# doorbellUSB.net
KiCad netlist of a schematic drawn in EAGLE
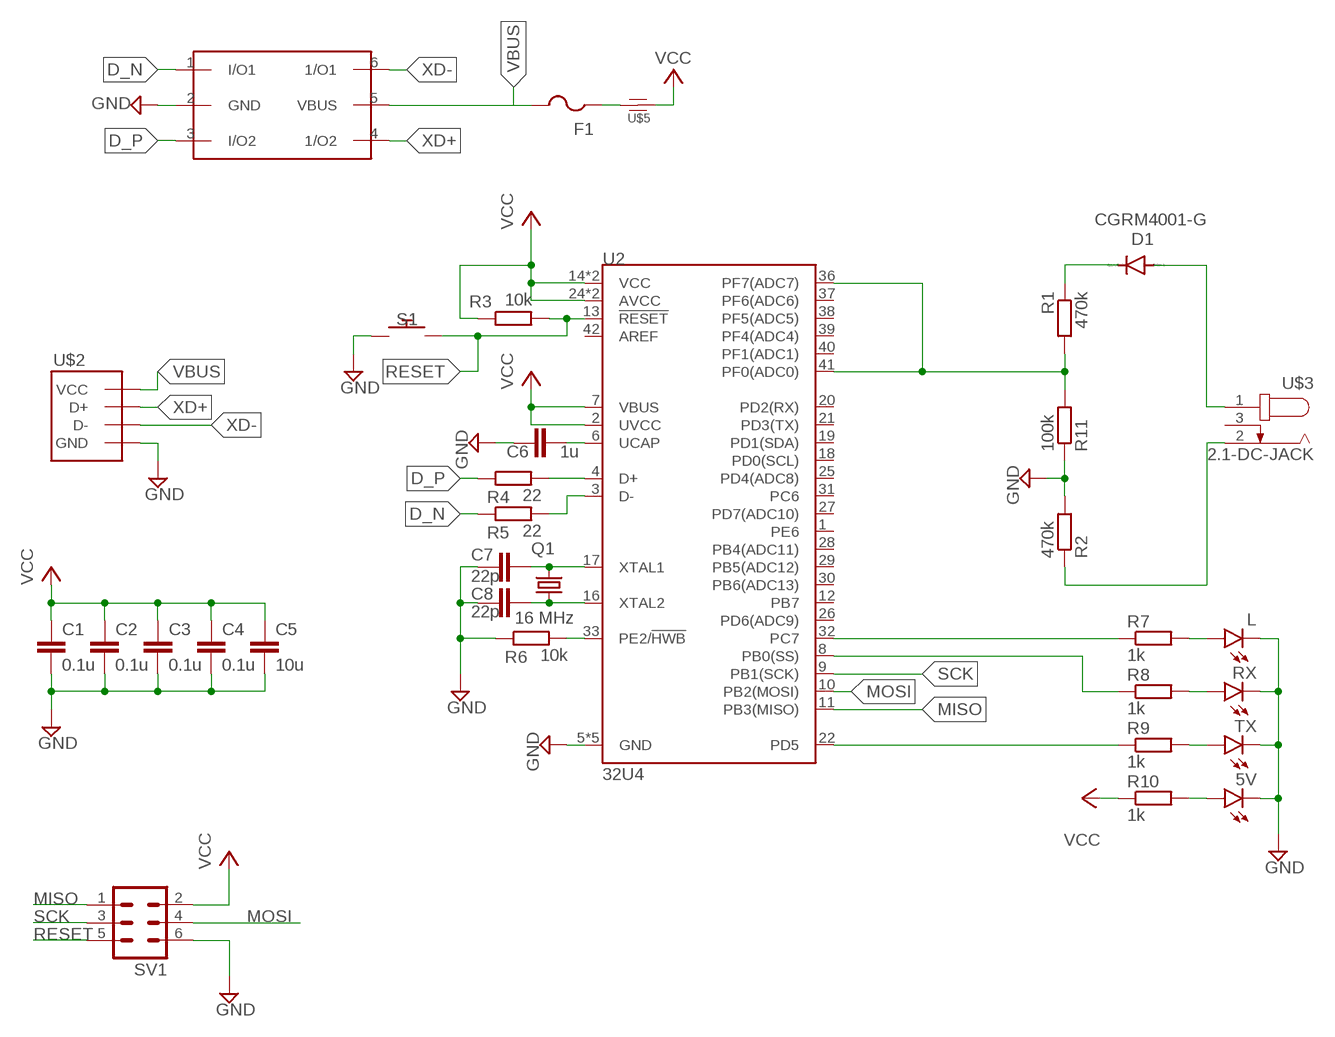
[diagram p0: schematic, sheet 1]

(export (version "E")
  (design (tool "Eeschema 10.0.6"))
  (components
    (comp (ref "5V")
      (value "LEDCHIP-LED0805")
      (footprint "eagle-import:CHIP-LED0805")
      (libsource (lib "eagle-import") (part "LEDCHIP-LED0805"))
    )
    (comp (ref "C1")
      (value "0.1u")
      (footprint "eagle-import:C0805")
      (libsource (lib "eagle-import") (part "C-EUC0805"))
    )
    (comp (ref "C2")
      (value "0.1u")
      (footprint "eagle-import:C0805")
      (libsource (lib "eagle-import") (part "C-EUC0805"))
    )
    (comp (ref "C3")
      (value "0.1u")
      (footprint "eagle-import:C0805")
      (libsource (lib "eagle-import") (part "C-EUC0805"))
    )
    (comp (ref "C4")
      (value "0.1u")
      (footprint "eagle-import:C0805")
      (libsource (lib "eagle-import") (part "C-EUC0805"))
    )
    (comp (ref "C5")
      (value "10u")
      (footprint "eagle-import:C0805")
      (libsource (lib "eagle-import") (part "C-EUC0805"))
    )
    (comp (ref "C6")
      (value "1u")
      (footprint "eagle-import:C0805")
      (libsource (lib "eagle-import") (part "C-EUC0805"))
    )
    (comp (ref "C7")
      (value "22p")
      (footprint "eagle-import:C0805")
      (libsource (lib "eagle-import") (part "C-EUC0805"))
    )
    (comp (ref "C8")
      (value "22p")
      (footprint "eagle-import:C0805")
      (libsource (lib "eagle-import") (part "C-EUC0805"))
    )
    (comp (ref "D1")
      (value "CGRM4001-G")
      (footprint "eagle-import:SOD-123_MINI-SMA")
      (libsource (lib "eagle-import") (part "CGRM400-G1"))
    )
    (comp (ref "F1")
      (value "PTCFUSE-1812")
      (footprint "eagle-import:1812")
      (libsource (lib "eagle-import") (part "PTCFUSE-1812"))
    )
    (comp (ref "L")
      (value "LEDCHIP-LED0805")
      (footprint "eagle-import:CHIP-LED0805")
      (libsource (lib "eagle-import") (part "LEDCHIP-LED0805"))
    )
    (comp (ref "Q1")
      (value "16 MHz")
      (footprint "eagle-import:5.0X3.2_2")
      (libsource (lib "eagle-import") (part "KX-9B"))
    )
    (comp (ref "R1")
      (value "470k")
      (footprint "eagle-import:R0805")
      (libsource (lib "eagle-import") (part "R-EU_R0805"))
    )
    (comp (ref "R2")
      (value "470k")
      (footprint "eagle-import:R0805")
      (libsource (lib "eagle-import") (part "R-EU_R0805"))
    )
    (comp (ref "R3")
      (value "10k")
      (footprint "eagle-import:R0805")
      (libsource (lib "eagle-import") (part "R-EU_R0805"))
    )
    (comp (ref "R4")
      (value "22")
      (footprint "eagle-import:R0805")
      (libsource (lib "eagle-import") (part "R-EU_R0805"))
    )
    (comp (ref "R5")
      (value "22")
      (footprint "eagle-import:R0805")
      (libsource (lib "eagle-import") (part "R-EU_R0805"))
    )
    (comp (ref "R6")
      (value "10k")
      (footprint "eagle-import:R0805")
      (libsource (lib "eagle-import") (part "R-EU_R0805"))
    )
    (comp (ref "R7")
      (value "1k")
      (footprint "eagle-import:R0805")
      (libsource (lib "eagle-import") (part "R-EU_R0805"))
    )
    (comp (ref "R8")
      (value "1k")
      (footprint "eagle-import:R0805")
      (libsource (lib "eagle-import") (part "R-EU_R0805"))
    )
    (comp (ref "R9")
      (value "1k")
      (footprint "eagle-import:R0805")
      (libsource (lib "eagle-import") (part "R-EU_R0805"))
    )
    (comp (ref "R10")
      (value "1k")
      (footprint "eagle-import:R0805")
      (libsource (lib "eagle-import") (part "R-EU_R0805"))
    )
    (comp (ref "R11")
      (value "100k")
      (footprint "eagle-import:R0805")
      (libsource (lib "eagle-import") (part "R-EU_R0805"))
    )
    (comp (ref "RX")
      (value "LEDCHIP-LED0805")
      (footprint "eagle-import:CHIP-LED0805")
      (libsource (lib "eagle-import") (part "LEDCHIP-LED0805"))
    )
    (comp (ref "S1")
      (value "3X4MM-PUHSBUTTON")
      (footprint "eagle-import:3X4MM-PUSHBUTTON")
      (libsource (lib "eagle-import") (part "3X4MM-PUHSBUTTON"))
    )
    (comp (ref "SV1")
      (value "MA03-2")
      (footprint "eagle-import:MA03-2")
      (libsource (lib "eagle-import") (part "MA03-2"))
    )
    (comp (ref "TX")
      (value "LEDCHIP-LED0805")
      (footprint "eagle-import:CHIP-LED0805")
      (libsource (lib "eagle-import") (part "LEDCHIP-LED0805"))
    )
    (comp (ref "U$1")
      (value "USBLC-2")
      (footprint "eagle-import:SOT23-6L")
      (libsource (lib "eagle-import") (part "USBLC-2"))
    )
    (comp (ref "U$2")
      (value "PCB-USB-A")
      (footprint "eagle-import:USB-A-ONBOARD")
      (libsource (lib "eagle-import") (part "PCB-USB-A"))
    )
    (comp (ref "U$3")
      (value "2.1-DC-JACK")
      (footprint "eagle-import:2.1X5.5MM_JACK")
      (libsource (lib "eagle-import") (part "2.1-DC-JACK"))
    )
    (comp (ref "U$5")
      (value "FERRITE-BEAD")
      (footprint "eagle-import:R0805")
      (libsource (lib "eagle-import") (part "FERRITE-BEAD"))
    )
    (comp (ref "U2")
      (value "32U4")
      (footprint "eagle-import:TQFP44")
      (libsource (lib "eagle-import") (part "ATMEGA32U4TQFP-44"))
    )
  )
  (nets
    (net (code "1") (name "D_N") (class "Default")
      (node (ref "R5") (pin "1") (pinfunction "1_1") (pintype "passive"))
      (node (ref "U$1") (pin "1") (pinfunction "I/O1_1") (pintype "bidirectional"))
    )
    (net (code "2") (name "D_P") (class "Default")
      (node (ref "R4") (pin "1") (pinfunction "1_1") (pintype "passive"))
      (node (ref "U$1") (pin "3") (pinfunction "I/O2_3") (pintype "bidirectional"))
    )
    (net (code "3") (name "GND") (class "Default")
      (node (ref "5V") (pin "C") (pinfunction "C_C") (pintype "passive"))
      (node (ref "C1") (pin "2") (pinfunction "2_2") (pintype "passive"))
      (node (ref "C2") (pin "2") (pinfunction "2_2") (pintype "passive"))
      (node (ref "C3") (pin "2") (pinfunction "2_2") (pintype "passive"))
      (node (ref "C4") (pin "2") (pinfunction "2_2") (pintype "passive"))
      (node (ref "C5") (pin "2") (pinfunction "2_2") (pintype "passive"))
      (node (ref "C6") (pin "1") (pinfunction "1_1") (pintype "passive"))
      (node (ref "C7") (pin "2") (pinfunction "2_2") (pintype "passive"))
      (node (ref "C8") (pin "2") (pinfunction "2_2") (pintype "passive"))
      (node (ref "L") (pin "C") (pinfunction "C_C") (pintype "passive"))
      (node (ref "R11") (pin "1") (pinfunction "1_1") (pintype "passive"))
      (node (ref "R2") (pin "2") (pinfunction "2_2") (pintype "passive"))
      (node (ref "R6") (pin "1") (pinfunction "1_1") (pintype "passive"))
      (node (ref "RX") (pin "C") (pinfunction "C_C") (pintype "passive"))
      (node (ref "S1") (pin "P$1") (pinfunction "P$1_P$1") (pintype "passive"))
      (node (ref "SV1") (pin "6") (pinfunction "6_6") (pintype "passive"))
      (node (ref "TX") (pin "C") (pinfunction "C_C") (pintype "passive"))
      (node (ref "U$1") (pin "2") (pinfunction "GND_2") (pintype "bidirectional"))
      (node (ref "U$2") (pin "GND") (pinfunction "GND_GND") (pintype "power_in"))
      (node (ref "U2") (pin "15") (pinfunction "GND_15") (pintype "bidirectional"))
      (node (ref "U2") (pin "23") (pinfunction "GND_23") (pintype "bidirectional"))
      (node (ref "U2") (pin "35") (pinfunction "GND_35") (pintype "bidirectional"))
      (node (ref "U2") (pin "43") (pinfunction "GND_43") (pintype "bidirectional"))
      (node (ref "U2") (pin "5") (pinfunction "GND_5") (pintype "bidirectional"))
    )
    (net (code "4") (name "MISO") (class "Default")
      (node (ref "SV1") (pin "1") (pinfunction "1_1") (pintype "passive"))
      (node (ref "U2") (pin "11") (pinfunction "PB3(MISO)_11") (pintype "bidirectional"))
    )
    (net (code "5") (name "MOSI") (class "Default")
      (node (ref "SV1") (pin "4") (pinfunction "4_4") (pintype "passive"))
      (node (ref "U2") (pin "10") (pinfunction "PB2(MOSI)_10") (pintype "bidirectional"))
    )
    (net (code "6") (name "Net-(5V-PadA)") (class "Default")
      (node (ref "5V") (pin "A") (pinfunction "A_A") (pintype "passive"))
      (node (ref "R10") (pin "2") (pinfunction "2_2") (pintype "passive"))
    )
    (net (code "7") (name "Net-(D1-PadA)") (class "Default")
      (node (ref "D1") (pin "A") (pinfunction "A_A") (pintype "passive"))
      (node (ref "U$3") (pin "1") (pinfunction "1_1") (pintype "passive"))
    )
    (net (code "8") (name "Net-(D1-PadC)") (class "Default")
      (node (ref "D1") (pin "C") (pinfunction "C_C") (pintype "passive"))
      (node (ref "R1") (pin "1") (pinfunction "1_1") (pintype "passive"))
    )
    (net (code "9") (name "Net-(F1-Pad1)") (class "Default")
      (node (ref "F1") (pin "1") (pinfunction "1_1") (pintype "passive"))
      (node (ref "U$5") (pin "2") (pinfunction "2_2") (pintype "bidirectional"))
    )
    (net (code "10") (name "Net-(L-PadA)") (class "Default")
      (node (ref "L") (pin "A") (pinfunction "A_A") (pintype "passive"))
      (node (ref "R7") (pin "2") (pinfunction "2_2") (pintype "passive"))
    )
    (net (code "11") (name "Net-(R2-Pad1)") (class "Default")
      (node (ref "R2") (pin "1") (pinfunction "1_1") (pintype "passive"))
      (node (ref "U$3") (pin "2") (pinfunction "2_2") (pintype "passive"))
    )
    (net (code "12") (name "Net-(R8-Pad2)") (class "Default")
      (node (ref "R8") (pin "2") (pinfunction "2_2") (pintype "passive"))
      (node (ref "RX") (pin "A") (pinfunction "A_A") (pintype "passive"))
    )
    (net (code "13") (name "Net-(R9-Pad2)") (class "Default")
      (node (ref "R9") (pin "2") (pinfunction "2_2") (pintype "passive"))
      (node (ref "TX") (pin "A") (pinfunction "A_A") (pintype "passive"))
    )
    (net (code "14") (name "Net-(U2-D+)") (class "Default")
      (node (ref "R4") (pin "2") (pinfunction "2_2") (pintype "passive"))
      (node (ref "U2") (pin "4") (pinfunction "D+_4") (pintype "bidirectional"))
    )
    (net (code "15") (name "Net-(U2-D-)") (class "Default")
      (node (ref "R5") (pin "2") (pinfunction "2_2") (pintype "passive"))
      (node (ref "U2") (pin "3") (pinfunction "D-_3") (pintype "bidirectional"))
    )
    (net (code "16") (name "Net-(U2-PB0(SS))") (class "Default")
      (node (ref "R8") (pin "1") (pinfunction "1_1") (pintype "passive"))
      (node (ref "U2") (pin "8") (pinfunction "PB0(SS)_8") (pintype "bidirectional"))
    )
    (net (code "17") (name "Net-(U2-PC7)") (class "Default")
      (node (ref "R7") (pin "1") (pinfunction "1_1") (pintype "passive"))
      (node (ref "U2") (pin "32") (pinfunction "PC7_32") (pintype "bidirectional"))
    )
    (net (code "18") (name "Net-(U2-PD5)") (class "Default")
      (node (ref "R9") (pin "1") (pinfunction "1_1") (pintype "passive"))
      (node (ref "U2") (pin "22") (pinfunction "PD5_22") (pintype "bidirectional"))
    )
    (net (code "19") (name "Net-(U2-PE2{slash}~{HWB})") (class "Default")
      (node (ref "R6") (pin "2") (pinfunction "2_2") (pintype "passive"))
      (node (ref "U2") (pin "33") (pinfunction "PE2/~{HWB}_33") (pintype "bidirectional"))
    )
    (net (code "20") (name "Net-(U2-PF0(ADC0))") (class "Default")
      (node (ref "R1") (pin "2") (pinfunction "2_2") (pintype "passive"))
      (node (ref "R11") (pin "2") (pinfunction "2_2") (pintype "passive"))
      (node (ref "U2") (pin "36") (pinfunction "PF7(ADC7)_36") (pintype "bidirectional"))
      (node (ref "U2") (pin "41") (pinfunction "PF0(ADC0)_41") (pintype "bidirectional"))
    )
    (net (code "21") (name "Net-(U2-UCAP)") (class "Default")
      (node (ref "C6") (pin "2") (pinfunction "2_2") (pintype "passive"))
      (node (ref "U2") (pin "6") (pinfunction "UCAP_6") (pintype "bidirectional"))
    )
    (net (code "22") (name "Net-(U2-XTAL1)") (class "Default")
      (node (ref "C7") (pin "1") (pinfunction "1_1") (pintype "passive"))
      (node (ref "Q1") (pin "2") (pinfunction "2_2") (pintype "passive"))
      (node (ref "U2") (pin "17") (pinfunction "XTAL1_17") (pintype "bidirectional"))
    )
    (net (code "23") (name "Net-(U2-XTAL2)") (class "Default")
      (node (ref "C8") (pin "1") (pinfunction "1_1") (pintype "passive"))
      (node (ref "Q1") (pin "1") (pinfunction "1_1") (pintype "passive"))
      (node (ref "U2") (pin "16") (pinfunction "XTAL2_16") (pintype "bidirectional"))
    )
    (net (code "24") (name "RESET") (class "Default")
      (node (ref "R3") (pin "2") (pinfunction "2_2") (pintype "passive"))
      (node (ref "S1") (pin "P$2") (pinfunction "P$2_P$2") (pintype "passive"))
      (node (ref "SV1") (pin "5") (pinfunction "5_5") (pintype "passive"))
      (node (ref "U2") (pin "13") (pinfunction "~{RESET}_13") (pintype "bidirectional"))
    )
    (net (code "25") (name "SCK") (class "Default")
      (node (ref "SV1") (pin "3") (pinfunction "3_3") (pintype "passive"))
      (node (ref "U2") (pin "9") (pinfunction "PB1(SCK)_9") (pintype "bidirectional"))
    )
    (net (code "26") (name "VBUS") (class "Default")
      (node (ref "F1") (pin "2") (pinfunction "2_2") (pintype "passive"))
      (node (ref "U$1") (pin "5") (pinfunction "VBUS_5") (pintype "bidirectional"))
      (node (ref "U$2") (pin "VCC") (pinfunction "VCC_VCC") (pintype "power_in"))
    )
    (net (code "27") (name "VCC") (class "Default")
      (node (ref "C1") (pin "1") (pinfunction "1_1") (pintype "passive"))
      (node (ref "C2") (pin "1") (pinfunction "1_1") (pintype "passive"))
      (node (ref "C3") (pin "1") (pinfunction "1_1") (pintype "passive"))
      (node (ref "C4") (pin "1") (pinfunction "1_1") (pintype "passive"))
      (node (ref "C5") (pin "1") (pinfunction "1_1") (pintype "passive"))
      (node (ref "R10") (pin "1") (pinfunction "1_1") (pintype "passive"))
      (node (ref "R3") (pin "1") (pinfunction "1_1") (pintype "passive"))
      (node (ref "SV1") (pin "2") (pinfunction "2_2") (pintype "passive"))
      (node (ref "U$5") (pin "1") (pinfunction "1_1") (pintype "bidirectional"))
      (node (ref "U2") (pin "14") (pinfunction "VCC_14") (pintype "bidirectional"))
      (node (ref "U2") (pin "2") (pinfunction "UVCC_2") (pintype "bidirectional"))
      (node (ref "U2") (pin "24") (pinfunction "AVCC_24") (pintype "bidirectional"))
      (node (ref "U2") (pin "34") (pinfunction "VCC_34") (pintype "bidirectional"))
      (node (ref "U2") (pin "44") (pinfunction "AVCC_44") (pintype "bidirectional"))
      (node (ref "U2") (pin "7") (pinfunction "VBUS_7") (pintype "bidirectional"))
    )
    (net (code "28") (name "XD+") (class "Default")
      (node (ref "U$1") (pin "4") (pinfunction "1/O2_4") (pintype "bidirectional"))
      (node (ref "U$2") (pin "D+") (pinfunction "D+_D+") (pintype "bidirectional"))
    )
    (net (code "29") (name "XD-") (class "Default")
      (node (ref "U$1") (pin "6") (pinfunction "1/O1_6") (pintype "bidirectional"))
      (node (ref "U$2") (pin "D-") (pinfunction "D-_D-") (pintype "bidirectional"))
    )
    (net (code "30") (name "unconnected-(U$3-Pad3)") (class "Default")
      (node (ref "U$3") (pin "3") (pinfunction "3_3") (pintype "passive"))
    )
    (net (code "31") (name "unconnected-(U2-AREF-Pad42)") (class "Default")
      (node (ref "U2") (pin "42") (pinfunction "AREF_42") (pintype "bidirectional"))
    )
    (net (code "32") (name "unconnected-(U2-PB4(ADC11)-Pad28)") (class "Default")
      (node (ref "U2") (pin "28") (pinfunction "PB4(ADC11)_28") (pintype "bidirectional"))
    )
    (net (code "33") (name "unconnected-(U2-PB5(ADC12)-Pad29)") (class "Default")
      (node (ref "U2") (pin "29") (pinfunction "PB5(ADC12)_29") (pintype "bidirectional"))
    )
    (net (code "34") (name "unconnected-(U2-PB6(ADC13)-Pad30)") (class "Default")
      (node (ref "U2") (pin "30") (pinfunction "PB6(ADC13)_30") (pintype "bidirectional"))
    )
    (net (code "35") (name "unconnected-(U2-PB7-Pad12)") (class "Default")
      (node (ref "U2") (pin "12") (pinfunction "PB7_12") (pintype "bidirectional"))
    )
    (net (code "36") (name "unconnected-(U2-PC6-Pad31)") (class "Default")
      (node (ref "U2") (pin "31") (pinfunction "PC6_31") (pintype "bidirectional"))
    )
    (net (code "37") (name "unconnected-(U2-PD0(SCL)-Pad18)") (class "Default")
      (node (ref "U2") (pin "18") (pinfunction "PD0(SCL)_18") (pintype "bidirectional"))
    )
    (net (code "38") (name "unconnected-(U2-PD1(SDA)-Pad19)") (class "Default")
      (node (ref "U2") (pin "19") (pinfunction "PD1(SDA)_19") (pintype "bidirectional"))
    )
    (net (code "39") (name "unconnected-(U2-PD2(RX)-Pad20)") (class "Default")
      (node (ref "U2") (pin "20") (pinfunction "PD2(RX)_20") (pintype "bidirectional"))
    )
    (net (code "40") (name "unconnected-(U2-PD3(TX)-Pad21)") (class "Default")
      (node (ref "U2") (pin "21") (pinfunction "PD3(TX)_21") (pintype "bidirectional"))
    )
    (net (code "41") (name "unconnected-(U2-PD4(ADC8)-Pad25)") (class "Default")
      (node (ref "U2") (pin "25") (pinfunction "PD4(ADC8)_25") (pintype "bidirectional"))
    )
    (net (code "42") (name "unconnected-(U2-PD6(ADC9)-Pad26)") (class "Default")
      (node (ref "U2") (pin "26") (pinfunction "PD6(ADC9)_26") (pintype "bidirectional"))
    )
    (net (code "43") (name "unconnected-(U2-PD7(ADC10)-Pad27)") (class "Default")
      (node (ref "U2") (pin "27") (pinfunction "PD7(ADC10)_27") (pintype "bidirectional"))
    )
    (net (code "44") (name "unconnected-(U2-PE6-Pad1)") (class "Default")
      (node (ref "U2") (pin "1") (pinfunction "PE6_1") (pintype "bidirectional"))
    )
    (net (code "45") (name "unconnected-(U2-PF1(ADC1)-Pad40)") (class "Default")
      (node (ref "U2") (pin "40") (pinfunction "PF1(ADC1)_40") (pintype "bidirectional"))
    )
    (net (code "46") (name "unconnected-(U2-PF4(ADC4)-Pad39)") (class "Default")
      (node (ref "U2") (pin "39") (pinfunction "PF4(ADC4)_39") (pintype "bidirectional"))
    )
    (net (code "47") (name "unconnected-(U2-PF5(ADC5)-Pad38)") (class "Default")
      (node (ref "U2") (pin "38") (pinfunction "PF5(ADC5)_38") (pintype "bidirectional"))
    )
    (net (code "48") (name "unconnected-(U2-PF6(ADC6)-Pad37)") (class "Default")
      (node (ref "U2") (pin "37") (pinfunction "PF6(ADC6)_37") (pintype "bidirectional"))
    )
  )
)
